# Sensor.net
KiCad netlist of a schematic drawn in Altium Designer
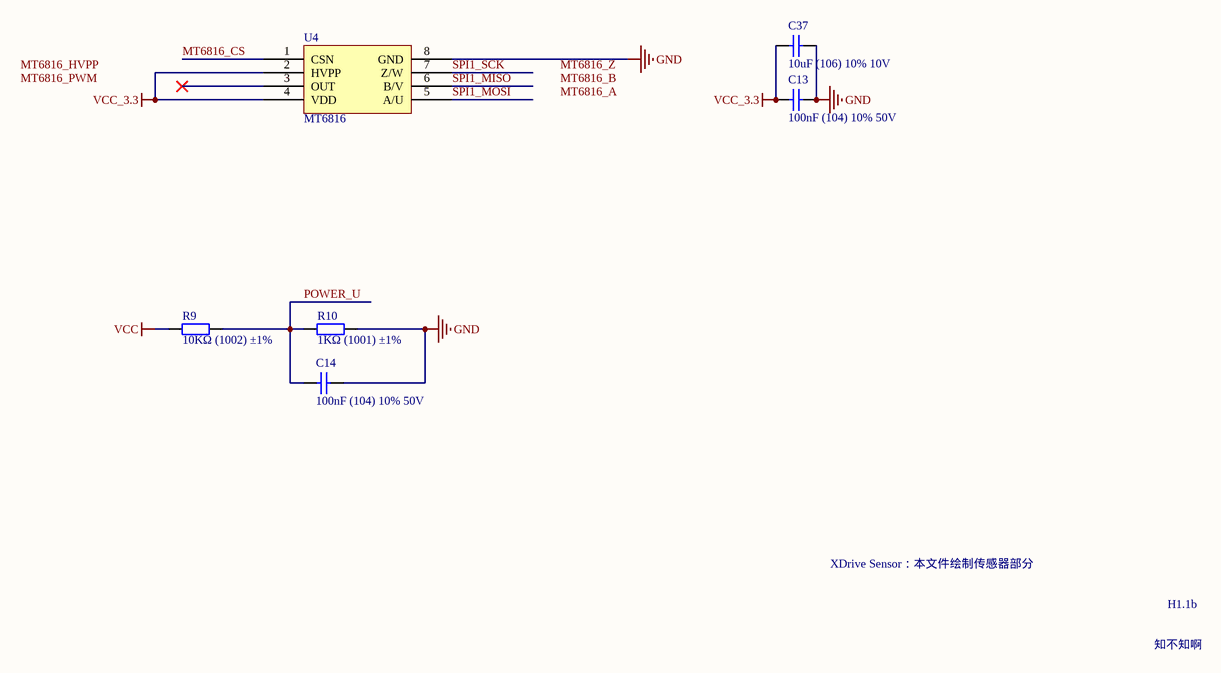
[diagram p0: Sensor.SchDoc]

(export (version "E")
  (design (tool "Eeschema 10.0.6"))
  (components
    (comp (ref "C13")
      (value "100nF (104) 10% 50V")
      (footprint "0603_C")
      (description "贴片电容")
      (libsource (lib "Miscellaneous Devices LC") (part "0603 100nF (104) 10% 50V"))
    )
    (comp (ref "C14")
      (value "100nF (104) 10% 50V")
      (footprint "0603_C")
      (description "贴片电容")
      (libsource (lib "Miscellaneous Devices LC") (part "0603 100nF (104) 10% 50V"))
    )
    (comp (ref "C37")
      (value "10uF (106) 10% 10V")
      (footprint "0603_C")
      (description "贴片电容")
      (libsource (lib "Miscellaneous Devices LC") (part "0603 10uF (106) 10% 10V"))
    )
    (comp (ref "R9")
      (value "10KΩ (1002) ±1%")
      (footprint "0603_R")
      (description "贴片电阻")
      (libsource (lib "Miscellaneous Devices LC") (part "0603 10KΩ (1002) 1%"))
    )
    (comp (ref "R10")
      (value "1KΩ (1001) ±1%")
      (footprint "0603_R")
      (description "贴片电阻")
      (libsource (lib "Miscellaneous Devices LC") (part "0603 1KΩ (1001) 1%"))
    )
    (comp (ref "U4")
      (value "MT6816")
      (footprint "SOIC_8")
      (description "磁角度传感器")
      (libsource (lib "Sensor") (part "MT6816"))
    )
  )
  (nets
    (net (code "3") (name "/MT6816_CS") (class "Default")
      (node (ref "U4") (pin "1") (pinfunction "CSN_1") (pintype "passive"))
    )
    (net (code "7") (name "/POWER_U") (class "Default")
      (node (ref "C14") (pin "1") (pinfunction "1_1") (pintype "passive"))
      (node (ref "R10") (pin "1") (pinfunction "1_1") (pintype "passive"))
      (node (ref "R9") (pin "2") (pinfunction "2_2") (pintype "passive"))
    )
    (net (code "8") (name "/SPI1_MISO") (class "Default")
      (node (ref "U4") (pin "6") (pinfunction "B/V_6") (pintype "passive"))
    )
    (net (code "9") (name "/SPI1_MOSI") (class "Default")
      (node (ref "U4") (pin "5") (pinfunction "A/U_5") (pintype "passive"))
    )
    (net (code "10") (name "/SPI1_SCK") (class "Default")
      (node (ref "U4") (pin "7") (pinfunction "Z/W_7") (pintype "passive"))
    )
    (net (code "11") (name "GND") (class "Default")
      (node (ref "C13") (pin "1") (pinfunction "1_1") (pintype "passive"))
      (node (ref "C14") (pin "2") (pinfunction "2_2") (pintype "passive"))
      (node (ref "C37") (pin "1") (pinfunction "1_1") (pintype "passive"))
      (node (ref "R10") (pin "2") (pinfunction "2_2") (pintype "passive"))
      (node (ref "U4") (pin "8") (pinfunction "GND_8") (pintype "passive"))
    )
    (net (code "12") (name "VCC") (class "Default")
      (node (ref "R9") (pin "1") (pinfunction "1_1") (pintype "passive"))
    )
    (net (code "13") (name "VCC_3.3") (class "Default")
      (node (ref "C13") (pin "2") (pinfunction "2_2") (pintype "passive"))
      (node (ref "C37") (pin "2") (pinfunction "2_2") (pintype "passive"))
      (node (ref "U4") (pin "2") (pinfunction "HVPP_2") (pintype "passive"))
      (node (ref "U4") (pin "4") (pinfunction "VDD_4") (pintype "passive"))
    )
    (net (code "14") (name "unconnected-(U4-OUT-Pad3)") (class "Default")
      (node (ref "U4") (pin "3") (pinfunction "OUT_3") (pintype "passive+no_connect"))
    )
  )
)
